# bmsMaster_usb.net
KiCad netlist of a schematic drawn in Altium Designer
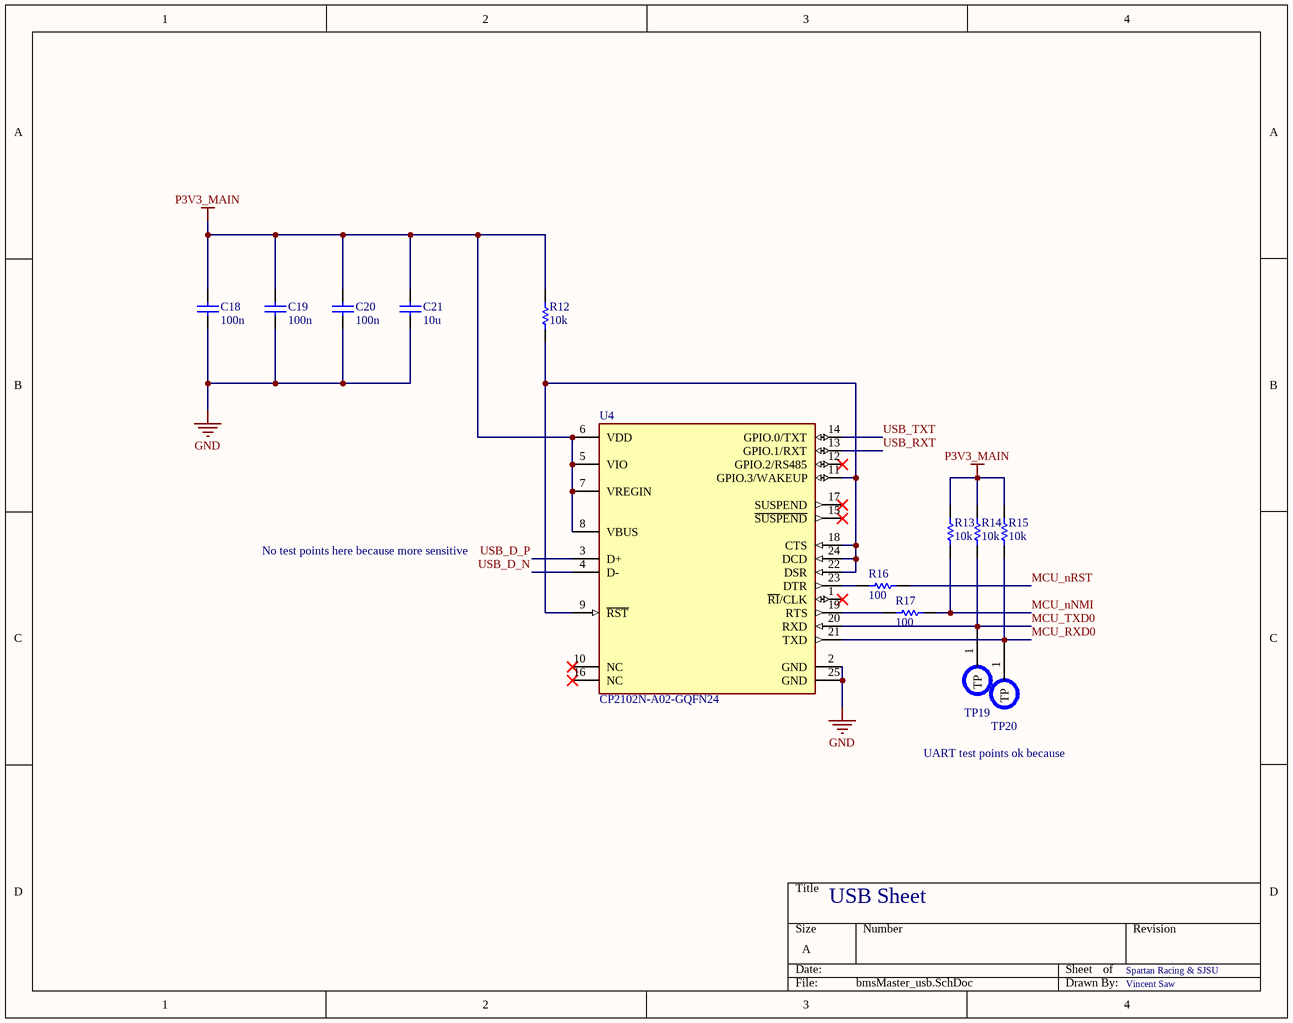
[diagram p0: bmsMaster_usb.SchDoc]

(export (version "E")
  (design (tool "Eeschema 10.0.6"))
  (components
    (comp (ref "C18")
      (value "100n")
      (footprint "CAPC1608X90N")
      (description "Capacitor")
      (libsource (lib "Simulation Generic Components") (part "Capacitor"))
    )
    (comp (ref "C19")
      (value "100n")
      (footprint "CAPC1608X90N")
      (description "Capacitor")
      (libsource (lib "Simulation Generic Components") (part "Capacitor"))
    )
    (comp (ref "C20")
      (value "100n")
      (footprint "CAPC1608X90N")
      (description "Capacitor")
      (libsource (lib "Simulation Generic Components") (part "Capacitor"))
    )
    (comp (ref "C21")
      (value "10u")
      (footprint "CAPC1608X90N")
      (description "Capacitor")
      (libsource (lib "Simulation Generic Components") (part "Capacitor"))
    )
    (comp (ref "R12")
      (value "10k")
      (footprint "RESC1608X50N")
      (description "Resistor")
      (libsource (lib "Simulation Generic Components") (part "Resistor"))
    )
    (comp (ref "R13")
      (value "10k")
      (footprint "RESC1608X50N")
      (description "Resistor")
      (libsource (lib "Simulation Generic Components") (part "Resistor"))
    )
    (comp (ref "R14")
      (value "10k")
      (footprint "RESC1608X50N")
      (description "Resistor")
      (libsource (lib "Simulation Generic Components") (part "Resistor"))
    )
    (comp (ref "R15")
      (value "10k")
      (footprint "RESC1608X50N")
      (description "Resistor")
      (libsource (lib "Simulation Generic Components") (part "Resistor"))
    )
    (comp (ref "R16")
      (value "100")
      (footprint "RESC1608X50N")
      (description "Resistor")
      (libsource (lib "Simulation Generic Components") (part "Resistor"))
    )
    (comp (ref "R17")
      (value "100")
      (footprint "RESC1608X50N")
      (description "Resistor")
      (libsource (lib "Simulation Generic Components") (part "Resistor"))
    )
    (comp (ref "TP19")
      (value "TSTPT")
      (footprint "Testpoint1")
      (libsource (lib "testpoint1") (part "Testpoint1"))
    )
    (comp (ref "TP20")
      (value "TSTPT")
      (footprint "Testpoint1")
      (libsource (lib "testpoint1") (part "Testpoint1"))
    )
    (comp (ref "U4")
      (value "CP2102N-A02-GQFN24")
      (footprint "FP-CP2102N-A02-GQFN24-MFG")
      (description "IC USB TO UART BRIDGE QFN24")
      (libsource (lib "Altium Content Vault") (part "132705adcabca70c0fc25feb25b66a0"))
    )
  )
  (nets
    (net (code "1") (name "/MCU_RXD0") (class "Default")
      (node (ref "R15") (pin "1") (pinfunction "1_1") (pintype "passive"))
      (node (ref "TP20") (pin "1") (pinfunction "TP_1") (pintype "passive"))
      (node (ref "U4") (pin "21") (pinfunction "TXD_21") (pintype "output"))
    )
    (net (code "2") (name "/MCU_TXD0") (class "Default")
      (node (ref "R14") (pin "1") (pinfunction "1_1") (pintype "passive"))
      (node (ref "TP19") (pin "1") (pinfunction "TP_1") (pintype "passive"))
      (node (ref "U4") (pin "20") (pinfunction "RXD_20") (pintype "input"))
    )
    (net (code "3") (name "/MCU_nNMI") (class "Default")
      (node (ref "R13") (pin "1") (pinfunction "1_1") (pintype "passive"))
      (node (ref "R17") (pin "1") (pinfunction "1_1") (pintype "passive"))
    )
    (net (code "4") (name "/MCU_nRST") (class "Default")
      (node (ref "R16") (pin "1") (pinfunction "1_1") (pintype "passive"))
    )
    (net (code "5") (name "/USB_D_N") (class "Default")
      (node (ref "U4") (pin "4") (pinfunction "D-_4") (pintype "passive"))
    )
    (net (code "6") (name "/USB_D_P") (class "Default")
      (node (ref "U4") (pin "3") (pinfunction "D+_3") (pintype "passive"))
    )
    (net (code "7") (name "/USB_RXT") (class "Default")
      (node (ref "U4") (pin "13") (pinfunction "GPIO.1/RXT_13") (pintype "bidirectional"))
    )
    (net (code "8") (name "/USB_TXT") (class "Default")
      (node (ref "U4") (pin "14") (pinfunction "GPIO.0/TXT_14") (pintype "bidirectional"))
    )
    (net (code "9") (name "GND") (class "Default")
      (node (ref "C18") (pin "1") (pinfunction "1_1") (pintype "passive"))
      (node (ref "C19") (pin "1") (pinfunction "1_1") (pintype "passive"))
      (node (ref "C20") (pin "1") (pinfunction "1_1") (pintype "passive"))
      (node (ref "C21") (pin "1") (pinfunction "1_1") (pintype "passive"))
      (node (ref "U4") (pin "2") (pinfunction "GND_2") (pintype "power_in"))
      (node (ref "U4") (pin "25") (pinfunction "GND_25") (pintype "power_in"))
    )
    (net (code "10") (name "Net-(U4-CTS)") (class "Default")
      (node (ref "R12") (pin "1") (pinfunction "1_1") (pintype "passive"))
      (node (ref "U4") (pin "11") (pinfunction "GPIO.3/WAKEUP_11") (pintype "bidirectional"))
      (node (ref "U4") (pin "18") (pinfunction "CTS_18") (pintype "input"))
      (node (ref "U4") (pin "22") (pinfunction "DSR_22") (pintype "input"))
      (node (ref "U4") (pin "24") (pinfunction "DCD_24") (pintype "input"))
      (node (ref "U4") (pin "9") (pinfunction "~{RST}_9") (pintype "input"))
    )
    (net (code "11") (name "Net-(U4-DTR)") (class "Default")
      (node (ref "R16") (pin "2") (pinfunction "2_2") (pintype "passive"))
      (node (ref "U4") (pin "23") (pinfunction "DTR_23") (pintype "output"))
    )
    (net (code "12") (name "Net-(U4-RTS)") (class "Default")
      (node (ref "R17") (pin "2") (pinfunction "2_2") (pintype "passive"))
      (node (ref "U4") (pin "19") (pinfunction "RTS_19") (pintype "output"))
    )
    (net (code "13") (name "P3V3_MAIN") (class "Default")
      (node (ref "C18") (pin "2") (pinfunction "2_2") (pintype "passive"))
      (node (ref "C19") (pin "2") (pinfunction "2_2") (pintype "passive"))
      (node (ref "C20") (pin "2") (pinfunction "2_2") (pintype "passive"))
      (node (ref "C21") (pin "2") (pinfunction "2_2") (pintype "passive"))
      (node (ref "R12") (pin "2") (pinfunction "2_2") (pintype "passive"))
      (node (ref "R13") (pin "2") (pinfunction "2_2") (pintype "passive"))
      (node (ref "R14") (pin "2") (pinfunction "2_2") (pintype "passive"))
      (node (ref "R15") (pin "2") (pinfunction "2_2") (pintype "passive"))
      (node (ref "U4") (pin "5") (pinfunction "VIO_5") (pintype "power_in"))
      (node (ref "U4") (pin "6") (pinfunction "VDD_6") (pintype "power_in"))
      (node (ref "U4") (pin "7") (pinfunction "VREGIN_7") (pintype "power_in"))
      (node (ref "U4") (pin "8") (pinfunction "VBUS_8") (pintype "power_in"))
    )
    (net (code "14") (name "unconnected-(U4-GPIO.2{slash}RS485-Pad12)") (class "Default")
      (node (ref "U4") (pin "12") (pinfunction "GPIO.2/RS485_12") (pintype "bidirectional+no_connect"))
    )
    (net (code "15") (name "unconnected-(U4-NC-Pad10)") (class "Default")
      (node (ref "U4") (pin "10") (pinfunction "NC_10") (pintype "passive+no_connect"))
    )
    (net (code "16") (name "unconnected-(U4-NC-Pad16)") (class "Default")
      (node (ref "U4") (pin "16") (pinfunction "NC_16") (pintype "passive+no_connect"))
    )
    (net (code "17") (name "unconnected-(U4-SUSPEND-Pad17)") (class "Default")
      (node (ref "U4") (pin "17") (pinfunction "SUSPEND_17") (pintype "output+no_connect"))
    )
    (net (code "18") (name "unconnected-(U4-~{RI}{slash}CLK-Pad1)") (class "Default")
      (node (ref "U4") (pin "1") (pinfunction "~{RI}/CLK_1") (pintype "bidirectional+no_connect"))
    )
    (net (code "19") (name "unconnected-(U4-~{SUSPEND}-Pad15)") (class "Default")
      (node (ref "U4") (pin "15") (pinfunction "~{SUSPEND}_15") (pintype "output+no_connect"))
    )
  )
)
